# drvinput6.net
KiCad netlist of a schematic drawn in Altium Designer
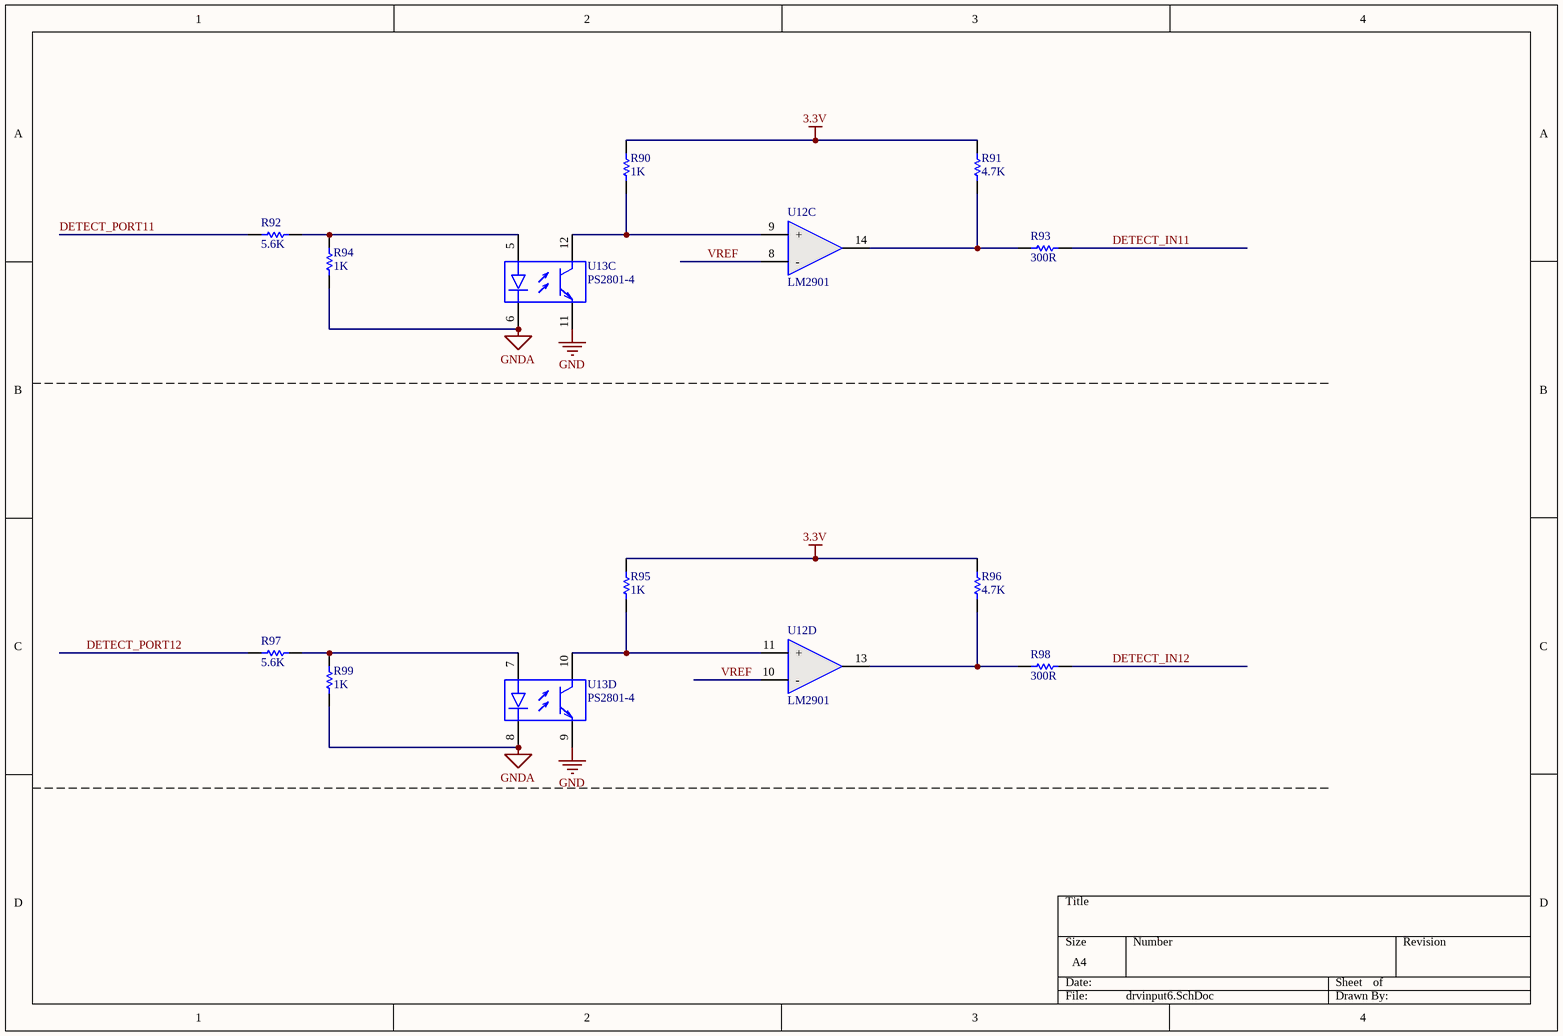
[diagram p0: drvinput6.SchDoc]

(export (version "E")
  (design (tool "Eeschema 10.0.6"))
  (components
    (comp (ref "R90")
      (value "1K")
      (footprint "RESC2012M")
      (description "Resistor")
      (fields (field (name "PUBLISHER") "Altium Limited"))
      (libsource (lib "Miscellaneous Devices") (part "Res1"))
    )
    (comp (ref "R91")
      (value "4.7K")
      (footprint "RESC2012M")
      (description "Resistor")
      (fields (field (name "PUBLISHER") "Altium Limited"))
      (libsource (lib "Miscellaneous Devices") (part "Res1"))
    )
    (comp (ref "R92")
      (value "5.6K")
      (footprint "RESC2012M")
      (description "Resistor")
      (fields (field (name "PUBLISHER") "Altium Limited"))
      (libsource (lib "Miscellaneous Devices") (part "Res1"))
    )
    (comp (ref "R93")
      (value "300R")
      (footprint "RESC2012M")
      (description "Resistor")
      (fields (field (name "PUBLISHER") "Altium Limited"))
      (libsource (lib "Miscellaneous Devices") (part "Res1"))
    )
    (comp (ref "R94")
      (value "1K")
      (footprint "RESC2012M")
      (description "Resistor")
      (fields (field (name "PUBLISHER") "Altium Limited"))
      (libsource (lib "Miscellaneous Devices") (part "Res1"))
    )
    (comp (ref "R95")
      (value "1K")
      (footprint "RESC2012M")
      (description "Resistor")
      (fields (field (name "PUBLISHER") "Altium Limited"))
      (libsource (lib "Miscellaneous Devices") (part "Res1"))
    )
    (comp (ref "R96")
      (value "4.7K")
      (footprint "RESC2012M")
      (description "Resistor")
      (fields (field (name "PUBLISHER") "Altium Limited"))
      (libsource (lib "Miscellaneous Devices") (part "Res1"))
    )
    (comp (ref "R97")
      (value "5.6K")
      (footprint "RESC2012M")
      (description "Resistor")
      (fields (field (name "PUBLISHER") "Altium Limited"))
      (libsource (lib "Miscellaneous Devices") (part "Res1"))
    )
    (comp (ref "R98")
      (value "300R")
      (footprint "RESC2012M")
      (description "Resistor")
      (fields (field (name "PUBLISHER") "Altium Limited"))
      (libsource (lib "Miscellaneous Devices") (part "Res1"))
    )
    (comp (ref "R99")
      (value "1K")
      (footprint "RESC2012M")
      (description "Resistor")
      (fields (field (name "PUBLISHER") "Altium Limited"))
      (libsource (lib "Miscellaneous Devices") (part "Res1"))
    )
    (comp (ref "U12")
      (value "LM2901")
      (footprint "SOIC-14AM")
      (description "4通道差分比较器芯片")
      (libsource (lib "UserSchDev") (part "LM2901"))
    )
    (comp (ref "U13")
      (value "PS2801-4")
      (footprint "SOIC16_N")
      (fields (field (name "PUBLISHER") "Altium Limited"))
      (libsource (lib "UserSchDev") (part "PS2801-4"))
    )
  )
  (nets
    (net (code "1") (name "/DETECT_IN11") (class "Default")
      (node (ref "R93") (pin "1") (pinfunction "1_1") (pintype "passive"))
    )
    (net (code "2") (name "/DETECT_IN12") (class "Default")
      (node (ref "R98") (pin "2") (pinfunction "2_2") (pintype "passive"))
    )
    (net (code "3") (name "/DETECT_PORT11") (class "Default")
      (node (ref "R92") (pin "2") (pinfunction "2_2") (pintype "passive"))
    )
    (net (code "4") (name "/DETECT_PORT12") (class "Default")
      (node (ref "R97") (pin "2") (pinfunction "2_2") (pintype "passive"))
    )
    (net (code "5") (name "/VREF") (class "Default")
      (node (ref "U12") (pin "10") (pinfunction "-_10") (pintype "passive"))
      (node (ref "U12") (pin "8") (pinfunction "-_8") (pintype "passive"))
    )
    (net (code "6") (name "3.3V") (class "Default")
      (node (ref "R90") (pin "1") (pinfunction "1_1") (pintype "passive"))
      (node (ref "R91") (pin "2") (pinfunction "2_2") (pintype "passive"))
      (node (ref "R95") (pin "1") (pinfunction "1_1") (pintype "passive"))
      (node (ref "R96") (pin "2") (pinfunction "2_2") (pintype "passive"))
    )
    (net (code "7") (name "GND") (class "Default")
      (node (ref "U13") (pin "11") (pinfunction "E_11") (pintype "passive"))
      (node (ref "U13") (pin "9") (pinfunction "E_9") (pintype "passive"))
    )
    (net (code "8") (name "GNDA") (class "Default")
      (node (ref "R94") (pin "1") (pinfunction "1_1") (pintype "passive"))
      (node (ref "R99") (pin "1") (pinfunction "1_1") (pintype "passive"))
      (node (ref "U13") (pin "6") (pinfunction "-_6") (pintype "passive"))
      (node (ref "U13") (pin "8") (pinfunction "-_8") (pintype "passive"))
    )
    (net (code "9") (name "Net-(U12C-+)") (class "Default")
      (node (ref "R90") (pin "2") (pinfunction "2_2") (pintype "passive"))
      (node (ref "U12") (pin "9") (pinfunction "+_9") (pintype "passive"))
      (node (ref "U13") (pin "12") (pinfunction "C_12") (pintype "passive"))
    )
    (net (code "10") (name "Net-(U12C-OUT)") (class "Default")
      (node (ref "R91") (pin "1") (pinfunction "1_1") (pintype "passive"))
      (node (ref "R93") (pin "2") (pinfunction "2_2") (pintype "passive"))
      (node (ref "U12") (pin "14") (pinfunction "OUT_14") (pintype "passive"))
    )
    (net (code "11") (name "Net-(U12D-+)") (class "Default")
      (node (ref "R95") (pin "2") (pinfunction "2_2") (pintype "passive"))
      (node (ref "U12") (pin "11") (pinfunction "+_11") (pintype "passive"))
      (node (ref "U13") (pin "10") (pinfunction "C_10") (pintype "passive"))
    )
    (net (code "12") (name "Net-(U12D-OUT)") (class "Default")
      (node (ref "R96") (pin "1") (pinfunction "1_1") (pintype "passive"))
      (node (ref "R98") (pin "1") (pinfunction "1_1") (pintype "passive"))
      (node (ref "U12") (pin "13") (pinfunction "OUT_13") (pintype "passive"))
    )
    (net (code "13") (name "Net-(U13C-+)") (class "Default")
      (node (ref "R92") (pin "1") (pinfunction "1_1") (pintype "passive"))
      (node (ref "R94") (pin "2") (pinfunction "2_2") (pintype "passive"))
      (node (ref "U13") (pin "5") (pinfunction "+_5") (pintype "passive"))
    )
    (net (code "14") (name "Net-(U13D-+)") (class "Default")
      (node (ref "R97") (pin "1") (pinfunction "1_1") (pintype "passive"))
      (node (ref "R99") (pin "2") (pinfunction "2_2") (pintype "passive"))
      (node (ref "U13") (pin "7") (pinfunction "+_7") (pintype "passive"))
    )
  )
)
